# Processor.net
KiCad netlist of a schematic drawn in Altium Designer
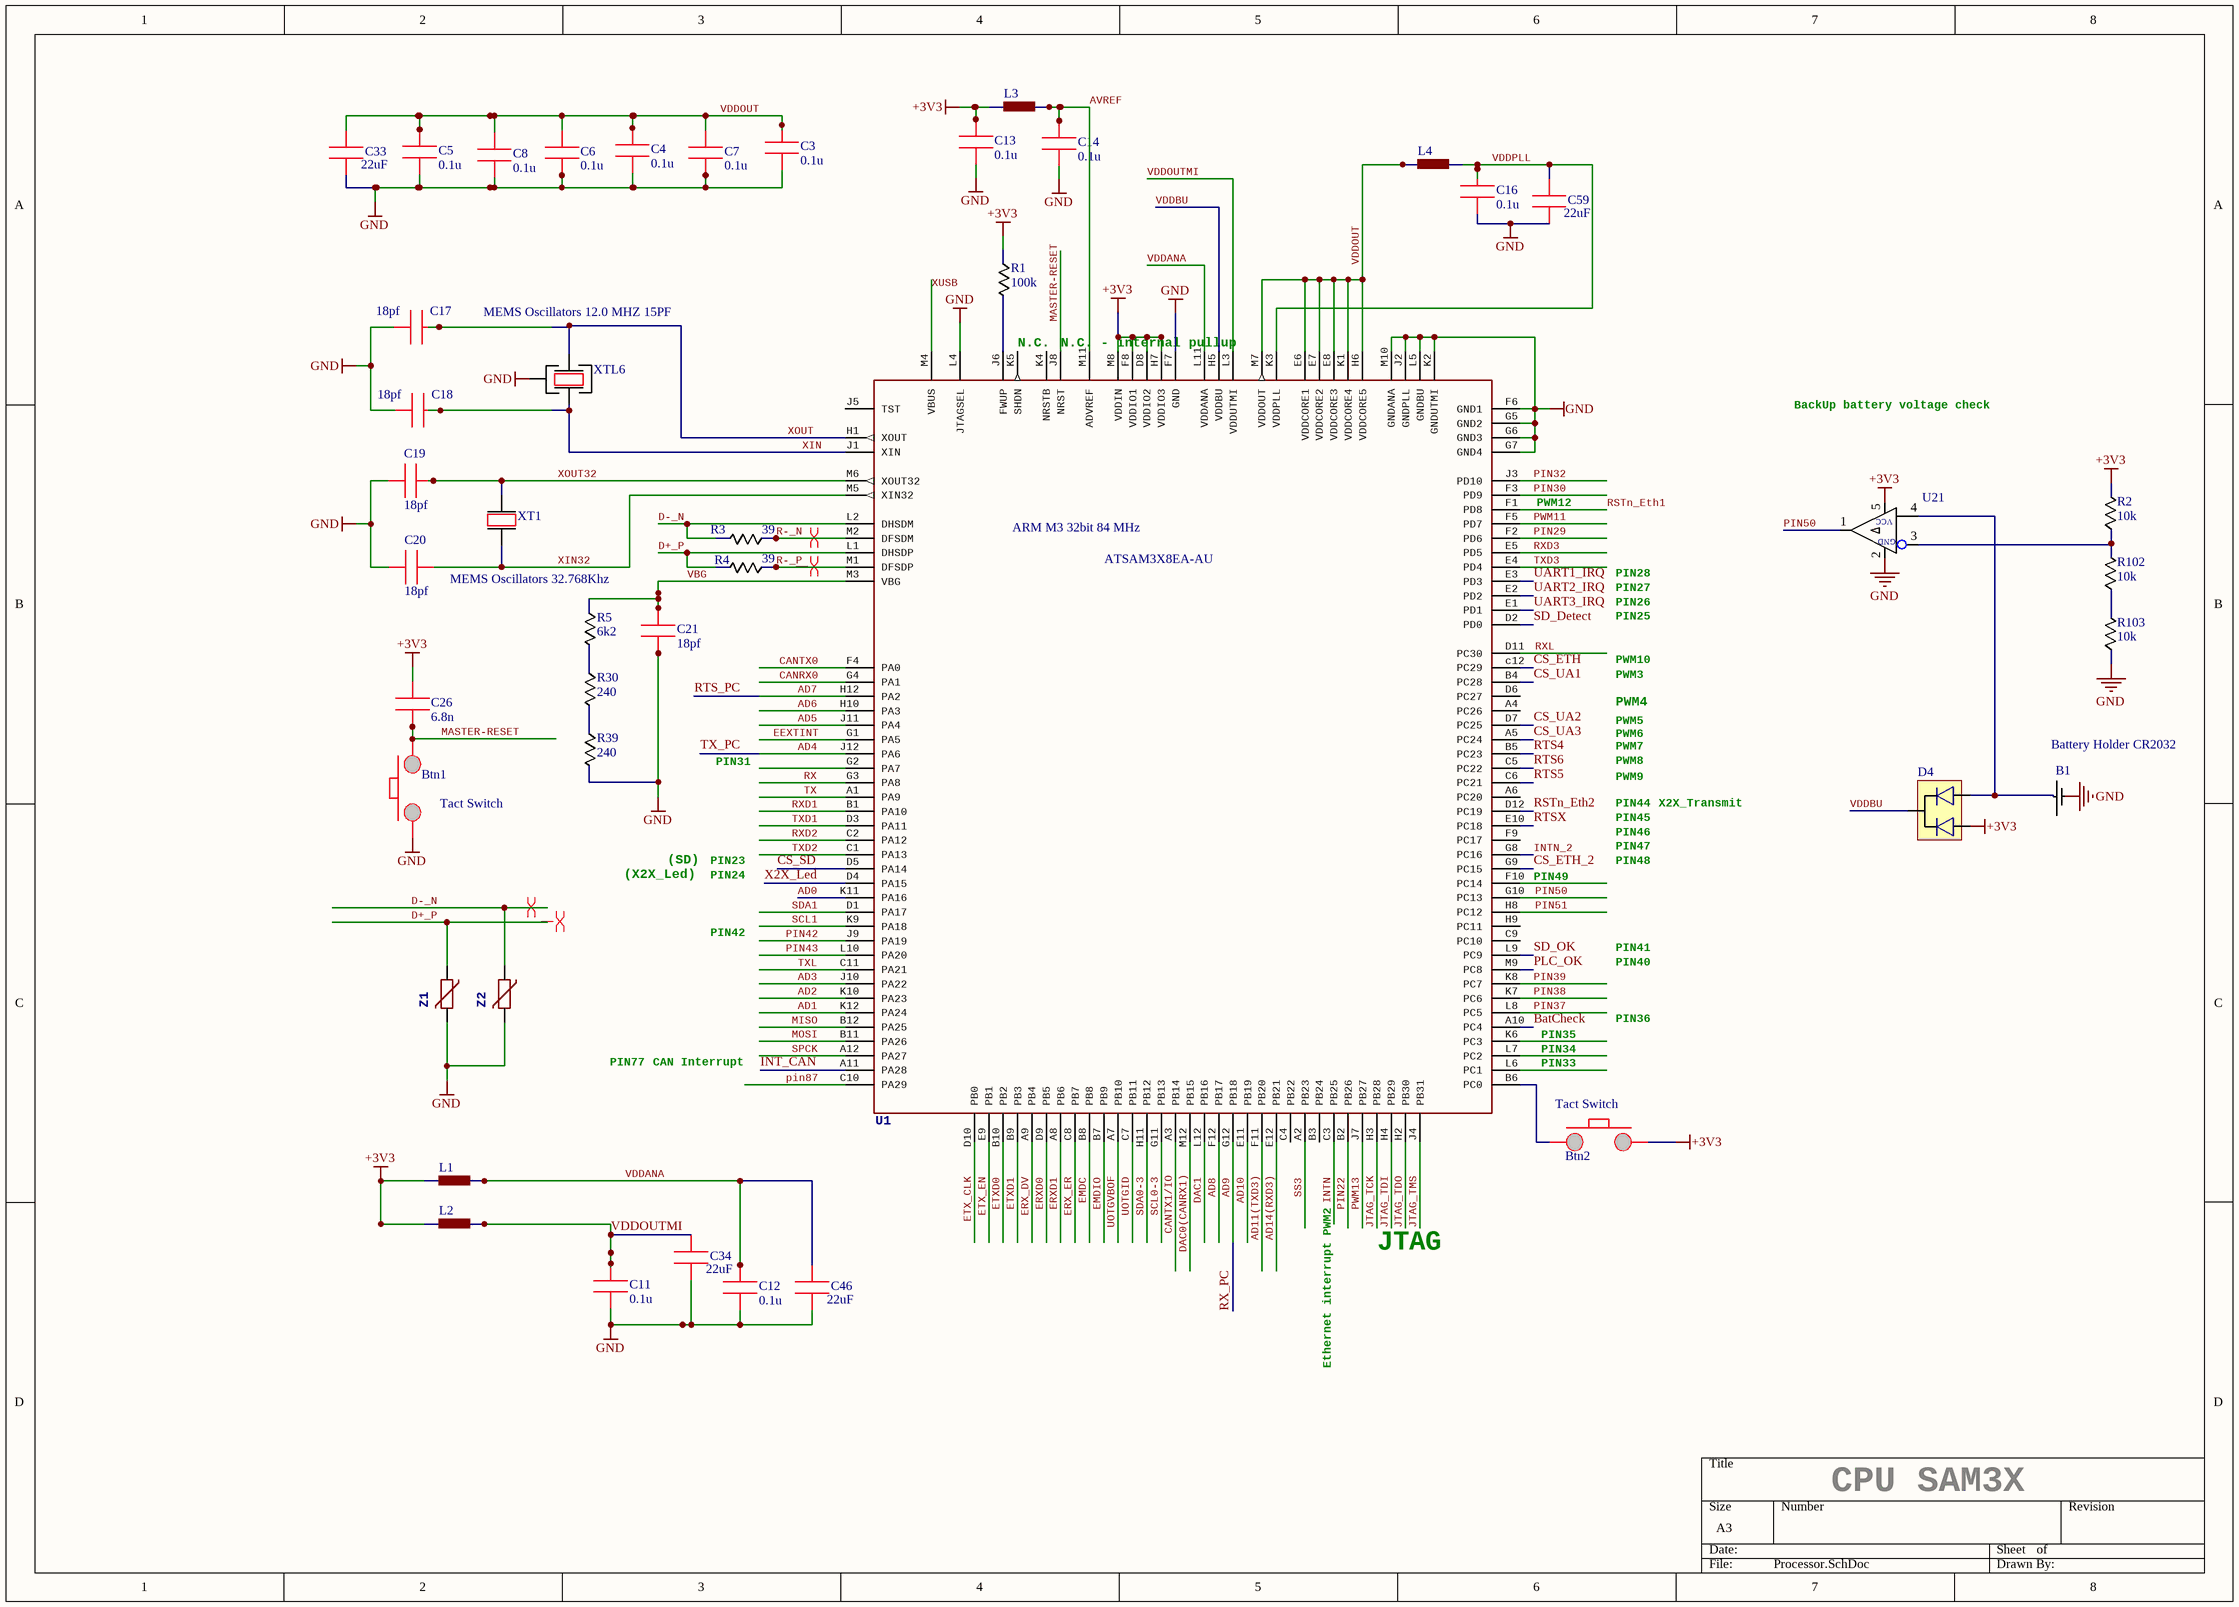
[diagram p0: Processor.SchDoc]

(export (version "E")
  (design (tool "Eeschema 10.0.6"))
  (components
    (comp (ref "B1")
      (value "~")
      (footprint "Batt Holder CR2032")
      (fields
        (field (name "PART DESCRIPTION") "Battery Holder CR2032")
        (field (name "PART NUMBER") "1734178-1")
      )
      (libsource (lib "kontr") (part "Batt Holder CR2032"))
    )
    (comp (ref "Btn1")
      (value "~")
      (footprint "Tact Switch")
      (fields
        (field (name "PART DESCRIPTION") "Tact Switch")
        (field (name "PART NUMBER") "KLS7-TS6606-4.3-180")
      )
      (libsource (lib "kontr") (part "Tact Switch"))
    )
    (comp (ref "Btn2")
      (value "~")
      (footprint "Tact Switch")
      (fields
        (field (name "PART DESCRIPTION") "Tact Switch")
        (field (name "PART NUMBER") "KLS7-TS6606-4.3-180")
      )
      (libsource (lib "kontr") (part "Tact Switch"))
    )
    (comp (ref "C3")
      (value "0.1u")
      (footprint "0603")
      (fields (field (name "PART NUMBER") "GRM188R72A104KA35D"))
      (libsource (lib "kontr") (part "Capasitor 0805"))
    )
    (comp (ref "C4")
      (value "0.1u")
      (footprint "0603")
      (fields (field (name "PART NUMBER") "GRM188R72A104KA35D"))
      (libsource (lib "kontr") (part "Capasitor 0805"))
    )
    (comp (ref "C5")
      (value "0.1u")
      (footprint "0603")
      (fields (field (name "PART NUMBER") "GRM188R72A104KA35D"))
      (libsource (lib "kontr") (part "Capasitor 0805"))
    )
    (comp (ref "C6")
      (value "0.1u")
      (footprint "0603")
      (fields (field (name "PART NUMBER") "GRM188R72A104KA35D"))
      (libsource (lib "kontr") (part "Capasitor 0805"))
    )
    (comp (ref "C7")
      (value "0.1u")
      (footprint "0603")
      (fields (field (name "PART NUMBER") "GRM188R72A104KA35D"))
      (libsource (lib "kontr") (part "Capasitor 0805"))
    )
    (comp (ref "C8")
      (value "0.1u")
      (footprint "0603")
      (fields (field (name "PART NUMBER") "GRM188R72A104KA35D"))
      (libsource (lib "kontr") (part "Capasitor 0805"))
    )
    (comp (ref "C11")
      (value "0.1u")
      (footprint "0603")
      (fields (field (name "PART NUMBER") "GRM188R72A104KA35D"))
      (libsource (lib "kontr") (part "Capasitor 0805"))
    )
    (comp (ref "C12")
      (value "0.1u")
      (footprint "0603")
      (fields (field (name "PART NUMBER") "GRM188R72A104KA35D"))
      (libsource (lib "kontr") (part "Capasitor 0805"))
    )
    (comp (ref "C13")
      (value "0.1u")
      (footprint "0603")
      (fields (field (name "PART NUMBER") "GRM188R72A104KA35D"))
      (libsource (lib "kontr") (part "Capasitor 0805"))
    )
    (comp (ref "C14")
      (value "0.1u")
      (footprint "0603")
      (fields (field (name "PART NUMBER") "GRM188R72A104KA35D"))
      (libsource (lib "kontr") (part "Capasitor 0805"))
    )
    (comp (ref "C16")
      (value "0.1u")
      (footprint "0603")
      (fields (field (name "PART NUMBER") "GRM188R72A104KA35D"))
      (libsource (lib "kontr") (part "Capasitor 0805"))
    )
    (comp (ref "C17")
      (value "18pf")
      (footprint "0603")
      (fields (field (name "PART NUMBER") "GRM1885C1H180JA01D"))
      (libsource (lib "kontr") (part "Capasitor 0805"))
    )
    (comp (ref "C18")
      (value "18pf")
      (footprint "0603")
      (fields (field (name "PART NUMBER") "GRM1885C1H180JA01D"))
      (libsource (lib "kontr") (part "Capasitor 0805"))
    )
    (comp (ref "C19")
      (value "18pf")
      (footprint "0603")
      (fields (field (name "PART NUMBER") "GRM1885C1H180JA01D"))
      (libsource (lib "kontr") (part "Capasitor 0805"))
    )
    (comp (ref "C20")
      (value "18pf")
      (footprint "0603")
      (fields (field (name "PART NUMBER") "GRM1885C1H180JA01D"))
      (libsource (lib "kontr") (part "Capasitor 0805"))
    )
    (comp (ref "C21")
      (value "18pf")
      (footprint "0603")
      (fields (field (name "PART NUMBER") "GRM1885C1H180JA01D"))
      (libsource (lib "kontr") (part "Capasitor 0805"))
    )
    (comp (ref "C26")
      (value "6.8n")
      (footprint "0603")
      (fields (field (name "PART NUMBER") "CC0603KRX7R9BB682"))
      (libsource (lib "kontr") (part "0603 CAP"))
    )
    (comp (ref "C33")
      (value "22uF")
      (footprint "1206")
      (fields (field (name "PART NUMBER") "CC1206KKX5R7BB226"))
      (libsource (lib "kontr") (part "0805 Cap"))
    )
    (comp (ref "C34")
      (value "22uF")
      (footprint "1206")
      (fields (field (name "PART NUMBER") "CC1206KKX5R7BB226"))
      (libsource (lib "kontr") (part "0805 Cap"))
    )
    (comp (ref "C46")
      (value "22uF")
      (footprint "1206")
      (fields (field (name "PART NUMBER") "CC1206KKX5R7BB226"))
      (libsource (lib "kontr") (part "0805 Cap"))
    )
    (comp (ref "C59")
      (value "22uF")
      (footprint "1206")
      (fields (field (name "PART NUMBER") "CC1206KKX5R7BB226"))
      (libsource (lib "kontr") (part "0805 Cap"))
    )
    (comp (ref "D4")
      (value "~")
      (footprint "SOT23")
      (fields (field (name "PART NUMBER") "BAT54C"))
      (libsource (lib "kontr") (part "BAT54C"))
    )
    (comp (ref "L1")
      (value "~")
      (footprint "0805")
      (fields (field (name "PART NUMBER") "BLM41PG102SN1L"))
      (libsource (lib "kontr") (part "BLM21PG220SN1D"))
    )
    (comp (ref "L2")
      (value "~")
      (footprint "0805")
      (fields (field (name "PART NUMBER") "BLM41PG102SN1L"))
      (libsource (lib "kontr") (part "BLM21PG220SN1D"))
    )
    (comp (ref "L3")
      (value "~")
      (footprint "0805")
      (fields (field (name "PART NUMBER") "BLM41PG102SN1L"))
      (libsource (lib "kontr") (part "BLM21PG220SN1D"))
    )
    (comp (ref "L4")
      (value "~")
      (footprint "0805")
      (fields (field (name "PART NUMBER") "BLM41PG102SN1L"))
      (libsource (lib "kontr") (part "BLM21PG220SN1D"))
    )
    (comp (ref "R1")
      (value "100k")
      (footprint "0603")
      (fields (field (name "PART NUMBER") "RC0603FR-07100KL"))
      (libsource (lib "kontr") (part "Resistor 0805"))
    )
    (comp (ref "R2")
      (value "10k")
      (footprint "0603")
      (fields (field (name "PART NUMBER") "RC0603JR-0710K"))
      (libsource (lib "kontr") (part "Resistor 0805"))
    )
    (comp (ref "R3")
      (value "39")
      (footprint "0603")
      (fields (field (name "PART NUMBER") "RC0603FR-0739RL"))
      (libsource (lib "kontr") (part "Resistor 0805"))
    )
    (comp (ref "R4")
      (value "39")
      (footprint "0603")
      (fields (field (name "PART NUMBER") "RC0603FR-0739RL"))
      (libsource (lib "kontr") (part "Resistor 0805"))
    )
    (comp (ref "R5")
      (value "6k2")
      (footprint "0603")
      (fields (field (name "PART NUMBER") "RC0603JR-076K2L"))
      (libsource (lib "kontr") (part "Resistor 0805"))
    )
    (comp (ref "R30")
      (value "240")
      (footprint "0603")
      (fields (field (name "PART NUMBER") "RC0603FR-07240RL"))
      (libsource (lib "kontr") (part "Resistor 0805"))
    )
    (comp (ref "R39")
      (value "240")
      (footprint "0603")
      (fields (field (name "PART NUMBER") "RC0603FR-07240RL"))
      (libsource (lib "kontr") (part "Resistor 0805"))
    )
    (comp (ref "R102")
      (value "10k")
      (footprint "0603")
      (fields (field (name "PART NUMBER") "RC0603JR-0710K"))
      (libsource (lib "kontr") (part "Resistor 0805"))
    )
    (comp (ref "R103")
      (value "10k")
      (footprint "0603")
      (fields (field (name "PART NUMBER") "RC0603JR-0710K"))
      (libsource (lib "kontr") (part "Resistor 0805"))
    )
    (comp (ref "U1")
      (value "~")
      (footprint "LFBGA 144")
      (fields
        (field (name "PART DESCRIPTION") "ARM M3 32bit 84 MHz")
        (field (name "PART NUMBER") "ATSAM3X8EA-AU")
      )
      (libsource (lib "SmartPrj") (part "ATSAM3X/AAU"))
    )
    (comp (ref "U21")
      (value "~")
      (footprint "SOT23 - 5 lead")
      (fields (field (name "PART NUMBER") "TS391ILT"))
      (libsource (lib "kontr") (part "TS391ILT"))
    )
    (comp (ref "XT1")
      (value "~")
      (footprint "KX – 327")
      (fields
        (field (name "PART DESCRIPTION") "MEMS Oscillators 32.768Khz")
        (field (name "PART NUMBER") "KX – 327XS")
      )
      (libsource (lib "kontr") (part "KX – 327XS"))
    )
    (comp (ref "XTL6")
      (value "~")
      (footprint "KX-7 XTAL")
      (fields
        (field (name "PART DESCRIPTION") "MEMS Oscillators 12.0 MHZ 15PF")
        (field (name "PART NUMBER") "Geyer KX-7 12.0 MHz")
      )
      (libsource (lib "kontr") (part "KX-7"))
    )
    (comp (ref "Z1")
      (value "~")
      (footprint "0603")
      (fields (field (name "PART NUMBER") "CG0603MLC-05E"))
      (libsource (lib "varistor") (part "VARISTORCN0603"))
    )
    (comp (ref "Z2")
      (value "~")
      (footprint "0603")
      (fields (field (name "PART NUMBER") "CG0603MLC-05E"))
      (libsource (lib "varistor") (part "VARISTORCN0603"))
    )
  )
  (nets
    (net (code "1") (name "+3V3") (class "Default")
      (node (ref "Btn2") (pin "1") (pinfunction "1_1") (pintype "passive"))
      (node (ref "C13") (pin "2") (pinfunction "2_2") (pintype "passive"))
      (node (ref "C26") (pin "2") (pinfunction "2_2") (pintype "passive"))
      (node (ref "D4") (pin "1") (pinfunction "1_1") (pintype "passive"))
      (node (ref "L1") (pin "1") (pintype "passive"))
      (node (ref "L2") (pin "1") (pintype "passive"))
      (node (ref "L3") (pin "1") (pintype "passive"))
      (node (ref "R1") (pin "1") (pintype "passive"))
      (node (ref "R2") (pin "2") (pintype "passive"))
      (node (ref "U1") (pin "D8") (pinfunction "VDDIO2_D8") (pintype "power_in"))
      (node (ref "U1") (pin "F8") (pinfunction "VDDIO1_F8") (pintype "power_in"))
      (node (ref "U1") (pin "H7") (pinfunction "VDDIO3_H7") (pintype "power_in"))
      (node (ref "U1") (pin "M8") (pinfunction "VDDIN_M8") (pintype "power_in"))
      (node (ref "U21") (pin "5") (pinfunction "7_5") (pintype "passive"))
    )
    (net (code "2") (name "/AD0") (class "Default")
      (node (ref "U1") (pin "K11") (pinfunction "PA16_K11") (pintype "passive"))
    )
    (net (code "3") (name "/AD1") (class "Default")
      (node (ref "U1") (pin "K12") (pinfunction "PA24_K12") (pintype "passive"))
    )
    (net (code "4") (name "/AD2") (class "Default")
      (node (ref "U1") (pin "K10") (pinfunction "PA23_K10") (pintype "passive"))
    )
    (net (code "5") (name "/AD3") (class "Default")
      (node (ref "U1") (pin "J10") (pinfunction "PA22_J10") (pintype "passive"))
    )
    (net (code "6") (name "/AD4") (class "Default")
      (node (ref "U1") (pin "J12") (pinfunction "PA6_J12") (pintype "passive"))
    )
    (net (code "7") (name "/AD5") (class "Default")
      (node (ref "U1") (pin "J11") (pinfunction "PA4_J11") (pintype "passive"))
    )
    (net (code "8") (name "/AD6") (class "Default")
      (node (ref "U1") (pin "H10") (pinfunction "PA3_H10") (pintype "passive"))
    )
    (net (code "9") (name "/AD7") (class "Default")
      (node (ref "U1") (pin "H12") (pinfunction "PA2_H12") (pintype "passive"))
    )
    (net (code "10") (name "/AD8") (class "Default")
      (node (ref "U1") (pin "F12") (pinfunction "PB17_F12") (pintype "passive"))
    )
    (net (code "11") (name "/AD9") (class "Default")
      (node (ref "U1") (pin "G12") (pinfunction "PB18_G12") (pintype "passive"))
    )
    (net (code "12") (name "/AD10") (class "Default")
      (node (ref "U1") (pin "E11") (pinfunction "PB19_E11") (pintype "passive"))
    )
    (net (code "13") (name "/AD11(TXD3)") (class "Default")
      (node (ref "U1") (pin "F11") (pinfunction "PB20_F11") (pintype "passive"))
    )
    (net (code "14") (name "/AD14(RXD3)") (class "Default")
      (node (ref "U1") (pin "E12") (pinfunction "PB21_E12") (pintype "passive"))
    )
    (net (code "15") (name "/AVREF") (class "Default")
      (node (ref "C14") (pin "2") (pinfunction "2_2") (pintype "passive"))
      (node (ref "L3") (pin "2") (pintype "passive"))
      (node (ref "U1") (pin "M11") (pinfunction "ADVREF_M11") (pintype "power_in"))
    )
    (net (code "16") (name "/BatCheck") (class "Default")
      (node (ref "U1") (pin "A10") (pinfunction "PC4_A10") (pintype "passive"))
    )
    (net (code "17") (name "/CANRX0") (class "Default")
      (node (ref "U1") (pin "G4") (pinfunction "PA1_G4") (pintype "passive"))
    )
    (net (code "18") (name "/CANTX0") (class "Default")
      (node (ref "U1") (pin "F4") (pinfunction "PA0_F4") (pintype "passive"))
    )
    (net (code "19") (name "/CANTX1{slash}IO") (class "Default")
      (node (ref "U1") (pin "A3") (pinfunction "PB14_A3") (pintype "passive"))
    )
    (net (code "20") (name "/CS_ETH") (class "Default")
      (node (ref "U1") (pin "c12") (pinfunction "PC29_c12") (pintype "passive"))
    )
    (net (code "21") (name "/CS_ETH_2") (class "Default")
      (node (ref "U1") (pin "G9") (pinfunction "PC15_G9") (pintype "passive"))
    )
    (net (code "22") (name "/CS_SD") (class "Default")
      (node (ref "U1") (pin "D5") (pinfunction "PA14_D5") (pintype "passive"))
    )
    (net (code "23") (name "/CS_UA1") (class "Default")
      (node (ref "U1") (pin "B4") (pinfunction "PC28_B4") (pintype "passive"))
    )
    (net (code "24") (name "/CS_UA2") (class "Default")
      (node (ref "U1") (pin "D7") (pinfunction "PC25_D7") (pintype "passive"))
    )
    (net (code "25") (name "/CS_UA3") (class "Default")
      (node (ref "U1") (pin "A5") (pinfunction "PC24_A5") (pintype "passive"))
    )
    (net (code "26") (name "/D+_P") (class "Default")
      (node (ref "R4") (pin "2") (pintype "passive"))
      (node (ref "U1") (pin "L1") (pinfunction "DHSDP_L1") (pintype "passive"))
      (node (ref "Z1") (pin "1") (pinfunction "1_1") (pintype "passive"))
    )
    (net (code "27") (name "/D-_N") (class "Default")
      (node (ref "R3") (pin "2") (pintype "passive"))
      (node (ref "U1") (pin "L2") (pinfunction "DHSDM_L2") (pintype "passive"))
      (node (ref "Z2") (pin "1") (pinfunction "1_1") (pintype "passive"))
    )
    (net (code "28") (name "/DAC0(CANRX1)") (class "Default")
      (node (ref "U1") (pin "M12") (pinfunction "PB15_M12") (pintype "passive"))
    )
    (net (code "29") (name "/DAC1") (class "Default")
      (node (ref "U1") (pin "L12") (pinfunction "PB16_L12") (pintype "passive"))
    )
    (net (code "30") (name "/EEXTINT") (class "Default")
      (node (ref "U1") (pin "G1") (pinfunction "PA5_G1") (pintype "passive"))
    )
    (net (code "31") (name "/EMDC") (class "Default")
      (node (ref "U1") (pin "B8") (pinfunction "PB8_B8") (pintype "passive"))
    )
    (net (code "32") (name "/EMDIO") (class "Default")
      (node (ref "U1") (pin "B7") (pinfunction "PB9_B7") (pintype "passive"))
    )
    (net (code "33") (name "/ERXD0") (class "Default")
      (node (ref "U1") (pin "D9") (pinfunction "PB5_D9") (pintype "passive"))
    )
    (net (code "34") (name "/ERXD1") (class "Default")
      (node (ref "U1") (pin "A8") (pinfunction "PB6_A8") (pintype "passive"))
    )
    (net (code "35") (name "/ERX_DV") (class "Default")
      (node (ref "U1") (pin "A9") (pinfunction "PB4_A9") (pintype "passive"))
    )
    (net (code "36") (name "/ERX_ER") (class "Default")
      (node (ref "U1") (pin "C8") (pinfunction "PB7_C8") (pintype "passive"))
    )
    (net (code "37") (name "/ETXD0") (class "Default")
      (node (ref "U1") (pin "B10") (pinfunction "PB2_B10") (pintype "passive"))
    )
    (net (code "38") (name "/ETXD1") (class "Default")
      (node (ref "U1") (pin "B9") (pinfunction "PB3_B9") (pintype "passive"))
    )
    (net (code "39") (name "/ETX_CLK") (class "Default")
      (node (ref "U1") (pin "D10") (pinfunction "PB0_D10") (pintype "passive"))
    )
    (net (code "40") (name "/ETX_EN") (class "Default")
      (node (ref "U1") (pin "E9") (pinfunction "PB1_E9") (pintype "passive"))
    )
    (net (code "41") (name "/INTN") (class "Default")
      (node (ref "U1") (pin "C3") (pinfunction "PB25_C3") (pintype "passive"))
    )
    (net (code "42") (name "/INTN_2") (class "Default")
      (node (ref "U1") (pin "G8") (pinfunction "PC16_G8") (pintype "passive"))
    )
    (net (code "43") (name "/INT_CAN") (class "Default")
      (node (ref "U1") (pin "A11") (pinfunction "PA28_A11") (pintype "passive"))
    )
    (net (code "44") (name "/JTAG_TCK") (class "Default")
      (node (ref "U1") (pin "H3") (pinfunction "PB28_H3") (pintype "passive"))
    )
    (net (code "45") (name "/JTAG_TDI") (class "Default")
      (node (ref "U1") (pin "H4") (pinfunction "PB29_H4") (pintype "passive"))
    )
    (net (code "46") (name "/JTAG_TDO") (class "Default")
      (node (ref "U1") (pin "H2") (pinfunction "PB30_H2") (pintype "passive"))
    )
    (net (code "47") (name "/JTAG_TMS") (class "Default")
      (node (ref "U1") (pin "J4") (pinfunction "PB31_J4") (pintype "passive"))
    )
    (net (code "48") (name "/MASTER-RESET") (class "Default")
      (node (ref "Btn1") (pin "1") (pinfunction "1_1") (pintype "passive"))
      (node (ref "C26") (pin "1") (pinfunction "1_1") (pintype "passive"))
      (node (ref "U1") (pin "J8") (pinfunction "NRST_J8") (pintype "passive"))
    )
    (net (code "49") (name "/MISO") (class "Default")
      (node (ref "U1") (pin "B12") (pinfunction "PA25_B12") (pintype "passive"))
    )
    (net (code "50") (name "/MOSI") (class "Default")
      (node (ref "U1") (pin "B11") (pinfunction "PA26_B11") (pintype "passive"))
    )
    (net (code "51") (name "/PIN22") (class "Default")
      (node (ref "U1") (pin "B2") (pinfunction "PB26_B2") (pintype "passive"))
    )
    (net (code "52") (name "/PIN29") (class "Default")
      (node (ref "U1") (pin "F2") (pinfunction "PD6_F2") (pintype "passive"))
    )
    (net (code "53") (name "/PIN30") (class "Default")
      (node (ref "U1") (pin "F3") (pinfunction "PD9_F3") (pintype "passive"))
    )
    (net (code "54") (name "/PIN32") (class "Default")
      (node (ref "U1") (pin "J3") (pinfunction "PD10_J3") (pintype "passive"))
    )
    (net (code "55") (name "/PIN37") (class "Default")
      (node (ref "U1") (pin "L8") (pinfunction "PC5_L8") (pintype "passive"))
    )
    (net (code "56") (name "/PIN38") (class "Default")
      (node (ref "U1") (pin "K7") (pinfunction "PC6_K7") (pintype "passive"))
    )
    (net (code "57") (name "/PIN39") (class "Default")
      (node (ref "U1") (pin "K8") (pinfunction "PC7_K8") (pintype "passive"))
    )
    (net (code "58") (name "/PIN42") (class "Default")
      (node (ref "U1") (pin "J9") (pinfunction "PA19_J9") (pintype "passive"))
    )
    (net (code "59") (name "/PIN43") (class "Default")
      (node (ref "U1") (pin "L10") (pinfunction "PA20_L10") (pintype "passive"))
    )
    (net (code "60") (name "/PIN50") (class "Default")
      (node (ref "U1") (pin "G10") (pinfunction "PC13_G10") (pintype "passive"))
      (node (ref "U21") (pin "1") (pinfunction "1_1") (pintype "passive"))
    )
    (net (code "61") (name "/PIN51") (class "Default")
      (node (ref "U1") (pin "H8") (pinfunction "PC12_H8") (pintype "passive"))
    )
    (net (code "62") (name "/PLC_OK") (class "Default")
      (node (ref "U1") (pin "M9") (pinfunction "PC8_M9") (pintype "passive"))
    )
    (net (code "63") (name "/PWM11") (class "Default")
      (node (ref "U1") (pin "F5") (pinfunction "PD7_F5") (pintype "passive"))
    )
    (net (code "64") (name "/PWM13") (class "Default")
      (node (ref "U1") (pin "J7") (pinfunction "PB27_J7") (pintype "passive"))
    )
    (net (code "65") (name "/R-_N") (class "Default")
      (node (ref "R3") (pin "1") (pintype "passive"))
      (node (ref "U1") (pin "M2") (pinfunction "DFSDM_M2") (pintype "passive"))
    )
    (net (code "66") (name "/R-_P") (class "Default")
      (node (ref "R4") (pin "1") (pintype "passive"))
      (node (ref "U1") (pin "M1") (pinfunction "DFSDP_M1") (pintype "passive"))
    )
    (net (code "67") (name "/RSTn_Eth1") (class "Default")
      (node (ref "U1") (pin "F1") (pinfunction "PD8_F1") (pintype "passive"))
    )
    (net (code "68") (name "/RSTn_Eth2") (class "Default")
      (node (ref "U1") (pin "D12") (pinfunction "PC19_D12") (pintype "passive"))
    )
    (net (code "69") (name "/RTS4") (class "Default")
      (node (ref "U1") (pin "B5") (pinfunction "PC23_B5") (pintype "passive"))
    )
    (net (code "70") (name "/RTS5") (class "Default")
      (node (ref "U1") (pin "C6") (pinfunction "PC21_C6") (pintype "passive"))
    )
    (net (code "71") (name "/RTS6") (class "Default")
      (node (ref "U1") (pin "C5") (pinfunction "PC22_C5") (pintype "passive"))
    )
    (net (code "72") (name "/RTSX") (class "Default")
      (node (ref "U1") (pin "E10") (pinfunction "PC18_E10") (pintype "passive"))
    )
    (net (code "73") (name "/RX") (class "Default")
      (node (ref "U1") (pin "G3") (pinfunction "PA8_G3") (pintype "passive"))
    )
    (net (code "74") (name "/RXD1") (class "Default")
      (node (ref "U1") (pin "B1") (pinfunction "PA10_B1") (pintype "passive"))
    )
    (net (code "75") (name "/RXD2") (class "Default")
      (node (ref "U1") (pin "C2") (pinfunction "PA12_C2") (pintype "passive"))
    )
    (net (code "76") (name "/RXD3") (class "Default")
      (node (ref "U1") (pin "E5") (pinfunction "PD5_E5") (pintype "passive"))
    )
    (net (code "77") (name "/RXL") (class "Default")
      (node (ref "U1") (pin "D11") (pinfunction "PC30_D11") (pintype "passive"))
    )
    (net (code "78") (name "/SCL0-3") (class "Default")
      (node (ref "U1") (pin "G11") (pinfunction "PB13_G11") (pintype "passive"))
    )
    (net (code "79") (name "/SCL1") (class "Default")
      (node (ref "U1") (pin "K9") (pinfunction "PA18_K9") (pintype "passive"))
    )
    (net (code "80") (name "/SDA0-3") (class "Default")
      (node (ref "U1") (pin "H11") (pinfunction "PB12_H11") (pintype "passive"))
    )
    (net (code "81") (name "/SDA1") (class "Default")
      (node (ref "U1") (pin "D1") (pinfunction "PA17_D1") (pintype "passive"))
    )
    (net (code "82") (name "/SD_Detect") (class "Default")
      (node (ref "U1") (pin "D2") (pinfunction "PD0_D2") (pintype "passive"))
    )
    (net (code "83") (name "/SD_OK") (class "Default")
      (node (ref "U1") (pin "L9") (pinfunction "PC9_L9") (pintype "passive"))
    )
    (net (code "84") (name "/SPCK") (class "Default")
      (node (ref "U1") (pin "A12") (pinfunction "PA27_A12") (pintype "passive"))
    )
    (net (code "85") (name "/SS3") (class "Default")
      (node (ref "U1") (pin "A2") (pinfunction "PB23_A2") (pintype "passive"))
    )
    (net (code "86") (name "/TX") (class "Default")
      (node (ref "U1") (pin "A1") (pinfunction "PA9_A1") (pintype "passive"))
    )
    (net (code "87") (name "/TXD1") (class "Default")
      (node (ref "U1") (pin "D3") (pinfunction "PA11_D3") (pintype "passive"))
    )
    (net (code "88") (name "/TXD2") (class "Default")
      (node (ref "U1") (pin "C1") (pinfunction "PA13_C1") (pintype "passive"))
    )
    (net (code "89") (name "/TXD3") (class "Default")
      (node (ref "U1") (pin "E4") (pinfunction "PD4_E4") (pintype "passive"))
    )
    (net (code "90") (name "/TXL") (class "Default")
      (node (ref "U1") (pin "C11") (pinfunction "PA21_C11") (pintype "passive"))
    )
    (net (code "91") (name "/UART1_IRQ") (class "Default")
      (node (ref "U1") (pin "E3") (pinfunction "PD3_E3") (pintype "passive"))
    )
    (net (code "92") (name "/UART2_IRQ") (class "Default")
      (node (ref "U1") (pin "E2") (pinfunction "PD2_E2") (pintype "passive"))
    )
    (net (code "93") (name "/UART3_IRQ") (class "Default")
      (node (ref "U1") (pin "E1") (pinfunction "PD1_E1") (pintype "passive"))
    )
    (net (code "94") (name "/UOTGID") (class "Default")
      (node (ref "U1") (pin "C7") (pinfunction "PB11_C7") (pintype "passive"))
    )
    (net (code "95") (name "/UOTGVBOF") (class "Default")
      (node (ref "U1") (pin "A7") (pinfunction "PB10_A7") (pintype "passive"))
    )
    (net (code "96") (name "/VBG") (class "Default")
      (node (ref "C21") (pin "2") (pinfunction "2_2") (pintype "passive"))
      (node (ref "R5") (pin "1") (pintype "passive"))
      (node (ref "U1") (pin "M3") (pinfunction "VBG_M3") (pintype "passive"))
    )
    (net (code "97") (name "/VDDANA") (class "Default")
      (node (ref "C12") (pin "2") (pinfunction "2_2") (pintype "passive"))
      (node (ref "C46") (pin "2") (pinfunction "2_2") (pintype "passive"))
      (node (ref "L1") (pin "2") (pintype "passive"))
      (node (ref "U1") (pin "L11") (pinfunction "VDDANA_L11") (pintype "power_in"))
    )
    (net (code "98") (name "/VDDBU") (class "Default")
      (node (ref "D4") (pin "3") (pinfunction "2_3") (pintype "passive"))
      (node (ref "U1") (pin "H5") (pinfunction "VDDBU_H5") (pintype "power_in"))
    )
    (net (code "99") (name "/VDDOUT") (class "Default")
      (node (ref "C3") (pin "2") (pinfunction "2_2") (pintype "passive"))
      (node (ref "C33") (pin "2") (pinfunction "2_2") (pintype "passive"))
      (node (ref "C4") (pin "2") (pinfunction "2_2") (pintype "passive"))
      (node (ref "C5") (pin "2") (pinfunction "2_2") (pintype "passive"))
      (node (ref "C6") (pin "2") (pinfunction "2_2") (pintype "passive"))
      (node (ref "C7") (pin "2") (pinfunction "2_2") (pintype "passive"))
      (node (ref "C8") (pin "2") (pinfunction "2_2") (pintype "passive"))
      (node (ref "L4") (pin "1") (pintype "passive"))
      (node (ref "U1") (pin "E6") (pinfunction "VDDCORE1_E6") (pintype "passive"))
      (node (ref "U1") (pin "E7") (pinfunction "VDDCORE2_E7") (pintype "passive"))
      (node (ref "U1") (pin "E8") (pinfunction "VDDCORE3_E8") (pintype "passive"))
      (node (ref "U1") (pin "H6") (pinfunction "VDDCORE5_H6") (pintype "passive"))
      (node (ref "U1") (pin "K1") (pinfunction "VDDCORE4_K1") (pintype "passive"))
      (node (ref "U1") (pin "M7") (pinfunction "VDDOUT_M7") (pintype "output"))
    )
    (net (code "100") (name "/VDDOUTMI") (class "Default")
      (node (ref "C11") (pin "2") (pinfunction "2_2") (pintype "passive"))
      (node (ref "C34") (pin "2") (pinfunction "2_2") (pintype "passive"))
      (node (ref "L2") (pin "2") (pintype "passive"))
      (node (ref "U1") (pin "L3") (pinfunction "VDDUTMI_L3") (pintype "passive"))
    )
    (net (code "101") (name "/VDDPLL") (class "Default")
      (node (ref "C16") (pin "2") (pinfunction "2_2") (pintype "passive"))
      (node (ref "C59") (pin "2") (pinfunction "2_2") (pintype "passive"))
      (node (ref "L4") (pin "2") (pintype "passive"))
      (node (ref "U1") (pin "K3") (pinfunction "VDDPLL_K3") (pintype "passive"))
    )
    (net (code "102") (name "/X2X_Led") (class "Default")
      (node (ref "U1") (pin "D4") (pinfunction "PA15_D4") (pintype "passive"))
    )
    (net (code "103") (name "/XIN") (class "Default")
      (node (ref "C18") (pin "2") (pinfunction "2_2") (pintype "passive"))
      (node (ref "U1") (pin "J1") (pinfunction "XIN_J1") (pintype "passive"))
      (node (ref "XTL6") (pin "3") (pinfunction "5_3") (pintype "passive"))
    )
    (net (code "104") (name "/XIN32") (class "Default")
      (node (ref "C20") (pin "1") (pinfunction "1_1") (pintype "passive"))
      (node (ref "U1") (pin "M5") (pinfunction "XIN32_M5") (pintype "output"))
      (node (ref "XT1") (pin "1") (pinfunction "5_1") (pintype "passive"))
    )
    (net (code "105") (name "/XOUT") (class "Default")
      (node (ref "C17") (pin "2") (pinfunction "2_2") (pintype "passive"))
      (node (ref "U1") (pin "H1") (pinfunction "XOUT_H1") (pintype "output"))
      (node (ref "XTL6") (pin "1") (pinfunction "5_1") (pintype "passive"))
    )
    (net (code "106") (name "/XOUT32") (class "Default")
      (node (ref "C19") (pin "1") (pinfunction "1_1") (pintype "passive"))
      (node (ref "U1") (pin "M6") (pinfunction "XOUT32_M6") (pintype "output"))
      (node (ref "XT1") (pin "2") (pinfunction "5_2") (pintype "passive"))
    )
    (net (code "107") (name "/XUSB") (class "Default")
      (node (ref "U1") (pin "M4") (pinfunction "VBUS_M4") (pintype "power_in"))
    )
    (net (code "108") (name "/pin87") (class "Default")
      (node (ref "U1") (pin "C10") (pinfunction "PA29_C10") (pintype "passive"))
    )
    (net (code "109") (name "GND") (class "Default")
      (node (ref "B1") (pin "0") (pinfunction "5_0") (pintype "passive"))
      (node (ref "Btn1") (pin "0") (pinfunction "0_0") (pintype "passive"))
      (node (ref "C11") (pin "1") (pinfunction "1_1") (pintype "passive"))
      (node (ref "C12") (pin "1") (pinfunction "1_1") (pintype "passive"))
      (node (ref "C13") (pin "1") (pinfunction "1_1") (pintype "passive"))
      (node (ref "C14") (pin "1") (pinfunction "1_1") (pintype "passive"))
      (node (ref "C16") (pin "1") (pinfunction "1_1") (pintype "passive"))
      (node (ref "C17") (pin "1") (pinfunction "1_1") (pintype "passive"))
      (node (ref "C18") (pin "1") (pinfunction "1_1") (pintype "passive"))
      (node (ref "C19") (pin "2") (pinfunction "2_2") (pintype "passive"))
      (node (ref "C20") (pin "2") (pinfunction "2_2") (pintype "passive"))
      (node (ref "C21") (pin "1") (pinfunction "1_1") (pintype "passive"))
      (node (ref "C3") (pin "1") (pinfunction "1_1") (pintype "passive"))
      (node (ref "C33") (pin "1") (pinfunction "1_1") (pintype "passive"))
      (node (ref "C34") (pin "1") (pinfunction "1_1") (pintype "passive"))
      (node (ref "C4") (pin "1") (pinfunction "1_1") (pintype "passive"))
      (node (ref "C46") (pin "1") (pinfunction "1_1") (pintype "passive"))
      (node (ref "C5") (pin "1") (pinfunction "1_1") (pintype "passive"))
      (node (ref "C59") (pin "1") (pinfunction "1_1") (pintype "passive"))
      (node (ref "C6") (pin "1") (pinfunction "1_1") (pintype "passive"))
      (node (ref "C7") (pin "1") (pinfunction "1_1") (pintype "passive"))
      (node (ref "C8") (pin "1") (pinfunction "1_1") (pintype "passive"))
      (node (ref "R103") (pin "1") (pintype "passive"))
      (node (ref "R39") (pin "2") (pintype "passive"))
      (node (ref "U1") (pin "F6") (pinfunction "GND1_F6") (pintype "power_in"))
      (node (ref "U1") (pin "F7") (pinfunction "GND_F7") (pintype "power_in"))
      (node (ref "U1") (pin "G5") (pinfunction "GND2_G5") (pintype "power_in"))
      (node (ref "U1") (pin "G6") (pinfunction "GND3_G6") (pintype "power_in"))
      (node (ref "U1") (pin "G7") (pinfunction "GND4_G7") (pintype "power_in"))
      (node (ref "U1") (pin "J2") (pinfunction "GNDPLL_J2") (pintype "power_in"))
      (node (ref "U1") (pin "K2") (pinfunction "GNDUTMI_K2") (pintype "power_in"))
      (node (ref "U1") (pin "L4") (pinfunction "JTAGSEL_L4") (pintype "passive"))
      (node (ref "U1") (pin "L5") (pinfunction "GNDBU_L5") (pintype "power_in"))
      (node (ref "U1") (pin "M10") (pinfunction "GNDANA_M10") (pintype "power_in"))
      (node (ref "U21") (pin "2") (pinfunction "2_2") (pintype "passive"))
      (node (ref "XTL6") (pin "2") (pinfunction "2_2") (pintype "passive"))
      (node (ref "Z1") (pin "2") (pinfunction "2_2") (pintype "passive"))
      (node (ref "Z2") (pin "2") (pinfunction "2_2") (pintype "passive"))
    )
    (net (code "110") (name "Net-(B1-6)") (class "Default")
      (node (ref "B1") (pin "1") (pinfunction "6_1") (pintype "passive"))
      (node (ref "D4") (pin "2") (pinfunction "2_2") (pintype "passive"))
      (node (ref "U21") (pin "4") (pinfunction "4_4") (pintype "passive"))
    )
    (net (code "111") (name "Net-(R30-Pad1)") (class "Default")
      (node (ref "R30") (pin "1") (pintype "passive"))
      (node (ref "R5") (pin "2") (pintype "passive"))
    )
    (net (code "112") (name "Net-(R30-Pad2)") (class "Default")
      (node (ref "R30") (pin "2") (pintype "passive"))
      (node (ref "R39") (pin "1") (pintype "passive"))
    )
    (net (code "113") (name "Net-(R102-Pad1)") (class "Default")
      (node (ref "R102") (pin "1") (pintype "passive"))
      (node (ref "R103") (pin "2") (pintype "passive"))
    )
    (net (code "114") (name "Net-(R102-Pad2)") (class "Default")
      (node (ref "R102") (pin "2") (pintype "passive"))
      (node (ref "R2") (pin "1") (pintype "passive"))
      (node (ref "U21") (pin "3") (pinfunction "3_3") (pintype "passive"))
    )
    (net (code "115") (name "Net-(U1-FWUP)") (class "Default")
      (node (ref "R1") (pin "2") (pintype "passive"))
      (node (ref "U1") (pin "J6") (pinfunction "FWUP_J6") (pintype "passive"))
    )
    (net (code "116") (name "Net-(U1-PC0)") (class "Default")
      (node (ref "Btn2") (pin "0") (pinfunction "0_0") (pintype "passive"))
      (node (ref "U1") (pin "B6") (pinfunction "PC0_B6") (pintype "passive"))
    )
    (net (code "117") (name "unconnected-(U1-NRSTB-PadK4)") (class "Default")
      (node (ref "U1") (pin "K4") (pinfunction "NRSTB_K4") (pintype "passive"))
    )
    (net (code "118") (name "unconnected-(U1-PA7-PadG2)") (class "Default")
      (node (ref "U1") (pin "G2") (pinfunction "PA7_G2") (pintype "passive"))
    )
    (net (code "119") (name "unconnected-(U1-PB22-PadC4)") (class "Default")
      (node (ref "U1") (pin "C4") (pinfunction "PB22_C4") (pintype "passive"))
    )
    (net (code "120") (name "unconnected-(U1-PB24-PadB3)") (class "Default")
      (node (ref "U1") (pin "B3") (pinfunction "PB24_B3") (pintype "passive"))
    )
    (net (code "121") (name "unconnected-(U1-PC1-PadL6)") (class "Default")
      (node (ref "U1") (pin "L6") (pinfunction "PC1_L6") (pintype "passive"))
    )
    (net (code "122") (name "unconnected-(U1-PC2-PadL7)") (class "Default")
      (node (ref "U1") (pin "L7") (pinfunction "PC2_L7") (pintype "passive"))
    )
    (net (code "123") (name "unconnected-(U1-PC3-PadK6)") (class "Default")
      (node (ref "U1") (pin "K6") (pinfunction "PC3_K6") (pintype "passive"))
    )
    (net (code "124") (name "unconnected-(U1-PC10-PadC9)") (class "Default")
      (node (ref "U1") (pin "C9") (pinfunction "PC10_C9") (pintype "passive"))
    )
    (net (code "125") (name "unconnected-(U1-PC11-PadH9)") (class "Default")
      (node (ref "U1") (pin "H9") (pinfunction "PC11_H9") (pintype "passive"))
    )
    (net (code "126") (name "unconnected-(U1-PC14-PadF10)") (class "Default")
      (node (ref "U1") (pin "F10") (pinfunction "PC14_F10") (pintype "passive"))
    )
    (net (code "127") (name "unconnected-(U1-PC17-PadF9)") (class "Default")
      (node (ref "U1") (pin "F9") (pinfunction "PC17_F9") (pintype "passive"))
    )
    (net (code "128") (name "unconnected-(U1-PC20-PadA6)") (class "Default")
      (node (ref "U1") (pin "A6") (pinfunction "PC20_A6") (pintype "passive"))
    )
    (net (code "129") (name "unconnected-(U1-PC26-PadA4)") (class "Default")
      (node (ref "U1") (pin "A4") (pinfunction "PC26_A4") (pintype "passive"))
    )
    (net (code "130") (name "unconnected-(U1-PC27-PadD6)") (class "Default")
      (node (ref "U1") (pin "D6") (pinfunction "PC27_D6") (pintype "passive"))
    )
    (net (code "131") (name "unconnected-(U1-SHDN-PadK5)") (class "Default")
      (node (ref "U1") (pin "K5") (pinfunction "SHDN_K5") (pintype "output"))
    )
    (net (code "132") (name "unconnected-(U1-TST-PadJ5)") (class "Default")
      (node (ref "U1") (pin "J5") (pinfunction "TST_J5") (pintype "passive"))
    )
  )
)
